# My_STM32_BOARD_ARDUINO_SCH.net
KiCad netlist of a schematic drawn in Altium Designer
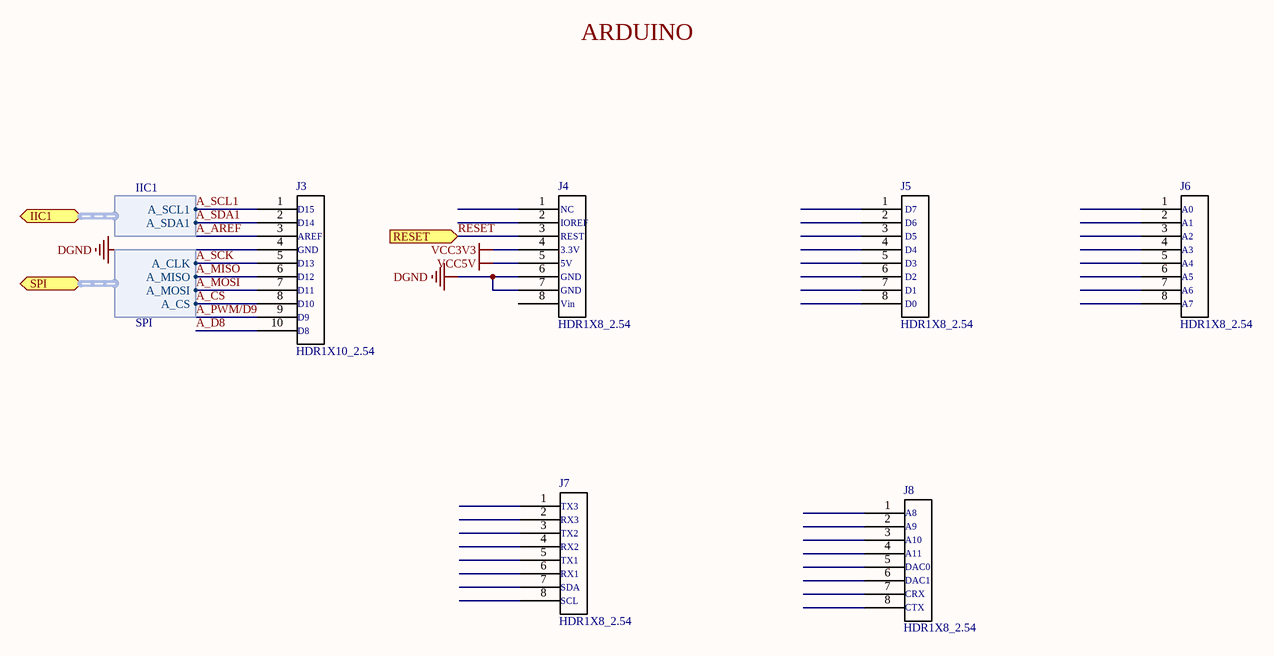
[diagram p0: My_STM32_BOARD_ARDUINO_SCH.SchDoc]

(export (version "E")
  (design (tool "Eeschema 10.0.6"))
  (components
    (comp (ref "J3")
      (value "HDR1X10_2.54")
      (footprint "HDR1X10_2.54_180")
      (libsource (lib "My_Integrated_Library") (part "HDR1X10_2.54"))
    )
    (comp (ref "J4")
      (value "HDR1X8_2.54")
      (footprint "HDR1X8_2.54_180")
      (libsource (lib "My_Integrated_Library") (part "HDR1X8_2.54"))
    )
    (comp (ref "J5")
      (value "HDR1X8_2.54")
      (footprint "HDR1X8_2.54_180")
      (libsource (lib "My_Integrated_Library") (part "HDR1X8_2.54"))
    )
    (comp (ref "J6")
      (value "HDR1X8_2.54")
      (footprint "HDR1X8_2.54_180")
      (libsource (lib "My_Integrated_Library") (part "HDR1X8_2.54"))
    )
    (comp (ref "J7")
      (value "HDR1X8_2.54")
      (footprint "HDR1X8_2.54_180")
      (libsource (lib "My_Integrated_Library") (part "HDR1X8_2.54"))
    )
    (comp (ref "J8")
      (value "HDR1X8_2.54")
      (footprint "HDR1X8_2.54_180")
      (libsource (lib "My_Integrated_Library") (part "HDR1X8_2.54"))
    )
  )
  (nets
    (net (code "3") (name "/A_AREF") (class "Default")
      (node (ref "J3") (pin "3") (pinfunction "3_3") (pintype "passive"))
    )
    (net (code "4") (name "/A_CS") (class "Default")
      (node (ref "J3") (pin "8") (pinfunction "8_8") (pintype "passive"))
    )
    (net (code "5") (name "/A_D8") (class "Default")
      (node (ref "J3") (pin "10") (pinfunction "10_10") (pintype "passive"))
    )
    (net (code "6") (name "/A_MISO") (class "Default")
      (node (ref "J3") (pin "6") (pinfunction "6_6") (pintype "passive"))
    )
    (net (code "7") (name "/A_MOSI") (class "Default")
      (node (ref "J3") (pin "7") (pinfunction "7_7") (pintype "passive"))
    )
    (net (code "8") (name "/A_PWM{slash}D9") (class "Default")
      (node (ref "J3") (pin "9") (pinfunction "9_9") (pintype "passive"))
    )
    (net (code "9") (name "/A_SCK") (class "Default")
      (node (ref "J3") (pin "5") (pinfunction "5_5") (pintype "passive"))
    )
    (net (code "10") (name "/A_SCL1") (class "Default")
      (node (ref "J3") (pin "1") (pinfunction "1_1") (pintype "passive"))
    )
    (net (code "11") (name "/A_SDA1") (class "Default")
      (node (ref "J3") (pin "2") (pinfunction "2_2") (pintype "passive"))
    )
    (net (code "12") (name "/RESET") (class "Default")
      (node (ref "J4") (pin "3") (pinfunction "3_3") (pintype "passive"))
    )
    (net (code "15") (name "DGND") (class "Default")
      (node (ref "J3") (pin "4") (pinfunction "4_4") (pintype "passive"))
      (node (ref "J4") (pin "6") (pinfunction "6_6") (pintype "passive"))
      (node (ref "J4") (pin "7") (pinfunction "7_7") (pintype "passive"))
    )
    (net (code "16") (name "VCC3V3") (class "Default")
      (node (ref "J4") (pin "4") (pinfunction "4_4") (pintype "passive"))
    )
    (net (code "17") (name "VCC5V") (class "Default")
      (node (ref "J4") (pin "5") (pinfunction "5_5") (pintype "passive"))
    )
    (net (code "18") (name "unconnected-(J4-Pad1)") (class "Default")
      (node (ref "J4") (pin "1") (pinfunction "1_1") (pintype "passive"))
    )
    (net (code "19") (name "unconnected-(J4-Pad2)") (class "Default")
      (node (ref "J4") (pin "2") (pinfunction "2_2") (pintype "passive"))
    )
    (net (code "20") (name "unconnected-(J4-Pad8)") (class "Default")
      (node (ref "J4") (pin "8") (pinfunction "8_8") (pintype "passive"))
    )
    (net (code "21") (name "unconnected-(J5-Pad1)") (class "Default")
      (node (ref "J5") (pin "1") (pinfunction "1_1") (pintype "passive"))
    )
    (net (code "22") (name "unconnected-(J5-Pad2)") (class "Default")
      (node (ref "J5") (pin "2") (pinfunction "2_2") (pintype "passive"))
    )
    (net (code "23") (name "unconnected-(J5-Pad3)") (class "Default")
      (node (ref "J5") (pin "3") (pinfunction "3_3") (pintype "passive"))
    )
    (net (code "24") (name "unconnected-(J5-Pad4)") (class "Default")
      (node (ref "J5") (pin "4") (pinfunction "4_4") (pintype "passive"))
    )
    (net (code "25") (name "unconnected-(J5-Pad5)") (class "Default")
      (node (ref "J5") (pin "5") (pinfunction "5_5") (pintype "passive"))
    )
    (net (code "26") (name "unconnected-(J5-Pad6)") (class "Default")
      (node (ref "J5") (pin "6") (pinfunction "6_6") (pintype "passive"))
    )
    (net (code "27") (name "unconnected-(J5-Pad7)") (class "Default")
      (node (ref "J5") (pin "7") (pinfunction "7_7") (pintype "passive"))
    )
    (net (code "28") (name "unconnected-(J5-Pad8)") (class "Default")
      (node (ref "J5") (pin "8") (pinfunction "8_8") (pintype "passive"))
    )
    (net (code "29") (name "unconnected-(J6-Pad1)") (class "Default")
      (node (ref "J6") (pin "1") (pinfunction "1_1") (pintype "passive"))
    )
    (net (code "30") (name "unconnected-(J6-Pad2)") (class "Default")
      (node (ref "J6") (pin "2") (pinfunction "2_2") (pintype "passive"))
    )
    (net (code "31") (name "unconnected-(J6-Pad3)") (class "Default")
      (node (ref "J6") (pin "3") (pinfunction "3_3") (pintype "passive"))
    )
    (net (code "32") (name "unconnected-(J6-Pad4)") (class "Default")
      (node (ref "J6") (pin "4") (pinfunction "4_4") (pintype "passive"))
    )
    (net (code "33") (name "unconnected-(J6-Pad5)") (class "Default")
      (node (ref "J6") (pin "5") (pinfunction "5_5") (pintype "passive"))
    )
    (net (code "34") (name "unconnected-(J6-Pad6)") (class "Default")
      (node (ref "J6") (pin "6") (pinfunction "6_6") (pintype "passive"))
    )
    (net (code "35") (name "unconnected-(J6-Pad7)") (class "Default")
      (node (ref "J6") (pin "7") (pinfunction "7_7") (pintype "passive"))
    )
    (net (code "36") (name "unconnected-(J6-Pad8)") (class "Default")
      (node (ref "J6") (pin "8") (pinfunction "8_8") (pintype "passive"))
    )
    (net (code "37") (name "unconnected-(J7-Pad1)") (class "Default")
      (node (ref "J7") (pin "1") (pinfunction "1_1") (pintype "passive"))
    )
    (net (code "38") (name "unconnected-(J7-Pad2)") (class "Default")
      (node (ref "J7") (pin "2") (pinfunction "2_2") (pintype "passive"))
    )
    (net (code "39") (name "unconnected-(J7-Pad3)") (class "Default")
      (node (ref "J7") (pin "3") (pinfunction "3_3") (pintype "passive"))
    )
    (net (code "40") (name "unconnected-(J7-Pad4)") (class "Default")
      (node (ref "J7") (pin "4") (pinfunction "4_4") (pintype "passive"))
    )
    (net (code "41") (name "unconnected-(J7-Pad5)") (class "Default")
      (node (ref "J7") (pin "5") (pinfunction "5_5") (pintype "passive"))
    )
    (net (code "42") (name "unconnected-(J7-Pad6)") (class "Default")
      (node (ref "J7") (pin "6") (pinfunction "6_6") (pintype "passive"))
    )
    (net (code "43") (name "unconnected-(J7-Pad7)") (class "Default")
      (node (ref "J7") (pin "7") (pinfunction "7_7") (pintype "passive"))
    )
    (net (code "44") (name "unconnected-(J7-Pad8)") (class "Default")
      (node (ref "J7") (pin "8") (pinfunction "8_8") (pintype "passive"))
    )
    (net (code "45") (name "unconnected-(J8-Pad1)") (class "Default")
      (node (ref "J8") (pin "1") (pinfunction "1_1") (pintype "passive"))
    )
    (net (code "46") (name "unconnected-(J8-Pad2)") (class "Default")
      (node (ref "J8") (pin "2") (pinfunction "2_2") (pintype "passive"))
    )
    (net (code "47") (name "unconnected-(J8-Pad3)") (class "Default")
      (node (ref "J8") (pin "3") (pinfunction "3_3") (pintype "passive"))
    )
    (net (code "48") (name "unconnected-(J8-Pad4)") (class "Default")
      (node (ref "J8") (pin "4") (pinfunction "4_4") (pintype "passive"))
    )
    (net (code "49") (name "unconnected-(J8-Pad5)") (class "Default")
      (node (ref "J8") (pin "5") (pinfunction "5_5") (pintype "passive"))
    )
    (net (code "50") (name "unconnected-(J8-Pad6)") (class "Default")
      (node (ref "J8") (pin "6") (pinfunction "6_6") (pintype "passive"))
    )
    (net (code "51") (name "unconnected-(J8-Pad7)") (class "Default")
      (node (ref "J8") (pin "7") (pinfunction "7_7") (pintype "passive"))
    )
    (net (code "52") (name "unconnected-(J8-Pad8)") (class "Default")
      (node (ref "J8") (pin "8") (pinfunction "8_8") (pintype "passive"))
    )
  )
)
